# i2c_7_segx4_display.net
KiCad netlist of a schematic drawn in EAGLE
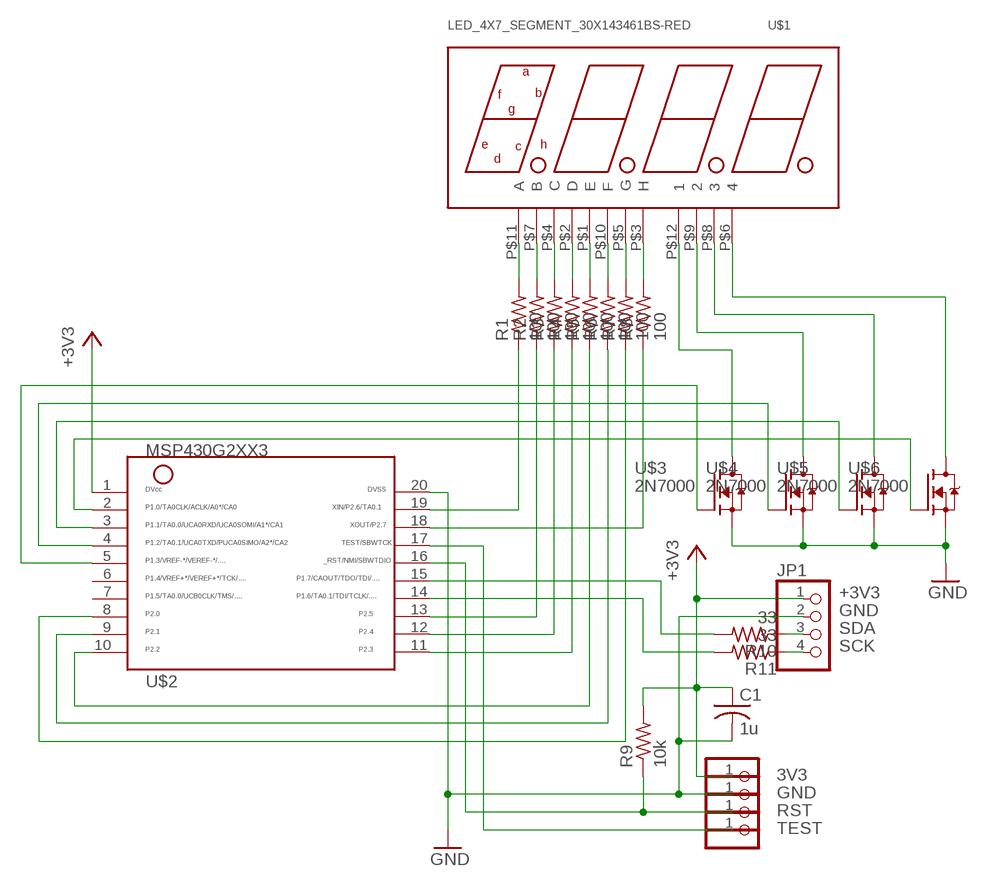
[diagram p0: schematic, sheet 1]

(export (version "E")
  (design (tool "Eeschema 10.0.6"))
  (components
    (comp (ref "3V3")
      (value "PINHD-1X1")
      (footprint "eagle-import:1X01")
      (libsource (lib "eagle-import") (part "PINHD-1X1"))
    )
    (comp (ref "C1")
      (value "1u")
      (footprint "eagle-import:C0805K")
      (libsource (lib "eagle-import") (part "C-USC0805K"))
    )
    (comp (ref "GND")
      (value "PINHD-1X1")
      (footprint "eagle-import:1X01")
      (libsource (lib "eagle-import") (part "PINHD-1X1"))
    )
    (comp (ref "JP1")
      (value "PINHD-1X4")
      (footprint "eagle-import:1X04")
      (libsource (lib "eagle-import") (part "PINHD-1X4"))
    )
    (comp (ref "R1")
      (value "100")
      (footprint "eagle-import:R0603")
      (libsource (lib "eagle-import") (part "R-US_R0603"))
    )
    (comp (ref "R2")
      (value "100")
      (footprint "eagle-import:R0603")
      (libsource (lib "eagle-import") (part "R-US_R0603"))
    )
    (comp (ref "R3")
      (value "100")
      (footprint "eagle-import:R0603")
      (libsource (lib "eagle-import") (part "R-US_R0603"))
    )
    (comp (ref "R4")
      (value "100")
      (footprint "eagle-import:R0603")
      (libsource (lib "eagle-import") (part "R-US_R0603"))
    )
    (comp (ref "R5")
      (value "100")
      (footprint "eagle-import:R0603")
      (libsource (lib "eagle-import") (part "R-US_R0603"))
    )
    (comp (ref "R6")
      (value "100")
      (footprint "eagle-import:R0603")
      (libsource (lib "eagle-import") (part "R-US_R0603"))
    )
    (comp (ref "R7")
      (value "100")
      (footprint "eagle-import:R0603")
      (libsource (lib "eagle-import") (part "R-US_R0603"))
    )
    (comp (ref "R8")
      (value "100")
      (footprint "eagle-import:R0603")
      (libsource (lib "eagle-import") (part "R-US_R0603"))
    )
    (comp (ref "R9")
      (value "10k")
      (footprint "eagle-import:R0603")
      (libsource (lib "eagle-import") (part "R-US_R0603"))
    )
    (comp (ref "R10")
      (value "33")
      (footprint "eagle-import:R0603")
      (libsource (lib "eagle-import") (part "R-US_R0603"))
    )
    (comp (ref "R11")
      (value "33")
      (footprint "eagle-import:R0603")
      (libsource (lib "eagle-import") (part "R-US_R0603"))
    )
    (comp (ref "RST")
      (value "PINHD-1X1")
      (footprint "eagle-import:1X01")
      (libsource (lib "eagle-import") (part "PINHD-1X1"))
    )
    (comp (ref "TEST")
      (value "PINHD-1X1")
      (footprint "eagle-import:1X01")
      (libsource (lib "eagle-import") (part "PINHD-1X1"))
    )
    (comp (ref "U$1")
      (value "LED_4X7_SEGMENT_30X143461BS-RED")
      (footprint "eagle-import:LED_4X7_SEGMENT_30X14")
      (libsource (lib "eagle-import") (part "LED_4X7_SEGMENT_30X143461BS-RED"))
    )
    (comp (ref "U$2")
      (value "G2553")
      (footprint "eagle-import:PW20")
      (libsource (lib "eagle-import") (part "G2XX3---PW20"))
    )
    (comp (ref "U$3")
      (value "2N7000")
      (footprint "eagle-import:SOT23")
      (libsource (lib "eagle-import") (part "2N7000"))
    )
    (comp (ref "U$4")
      (value "2N7000")
      (footprint "eagle-import:SOT23")
      (libsource (lib "eagle-import") (part "2N7000"))
    )
    (comp (ref "U$5")
      (value "2N7000")
      (footprint "eagle-import:SOT23")
      (libsource (lib "eagle-import") (part "2N7000"))
    )
    (comp (ref "U$6")
      (value "2N7000")
      (footprint "eagle-import:SOT23")
      (libsource (lib "eagle-import") (part "2N7000"))
    )
  )
  (nets
    (net (code "1") (name "+3V3") (class "Default")
      (node (ref "3V3") (pin "1") (pinfunction "1_1") (pintype "passive"))
      (node (ref "C1") (pin "1") (pinfunction "1_1") (pintype "passive"))
      (node (ref "JP1") (pin "1") (pinfunction "1_1") (pintype "passive"))
      (node (ref "R9") (pin "2") (pinfunction "2_2") (pintype "passive"))
      (node (ref "U$2") (pin "1") (pinfunction "1_1") (pintype "bidirectional"))
    )
    (net (code "2") (name "/SCK") (class "Default")
      (node (ref "JP1") (pin "4") (pinfunction "4_4") (pintype "passive"))
      (node (ref "R11") (pin "1") (pinfunction "1_1") (pintype "passive"))
    )
    (net (code "3") (name "/SDA") (class "Default")
      (node (ref "JP1") (pin "3") (pinfunction "3_3") (pintype "passive"))
      (node (ref "R10") (pin "1") (pinfunction "1_1") (pintype "passive"))
    )
    (net (code "4") (name "GND") (class "Default")
      (node (ref "C1") (pin "2") (pinfunction "2_2") (pintype "passive"))
      (node (ref "GND") (pin "1") (pinfunction "1_1") (pintype "passive"))
      (node (ref "JP1") (pin "2") (pinfunction "2_2") (pintype "passive"))
      (node (ref "U$2") (pin "20") (pinfunction "20_20") (pintype "bidirectional"))
      (node (ref "U$3") (pin "2") (pinfunction "S_2") (pintype "passive"))
      (node (ref "U$4") (pin "2") (pinfunction "S_2") (pintype "passive"))
      (node (ref "U$5") (pin "2") (pinfunction "S_2") (pintype "passive"))
      (node (ref "U$6") (pin "2") (pinfunction "S_2") (pintype "passive"))
    )
    (net (code "5") (name "Net-(R1-Pad1)") (class "Default")
      (node (ref "R1") (pin "1") (pinfunction "1_1") (pintype "passive"))
      (node (ref "U$2") (pin "19") (pinfunction "19_19") (pintype "bidirectional"))
    )
    (net (code "6") (name "Net-(R2-Pad1)") (class "Default")
      (node (ref "R2") (pin "1") (pinfunction "1_1") (pintype "passive"))
      (node (ref "U$2") (pin "13") (pinfunction "13_13") (pintype "bidirectional"))
    )
    (net (code "7") (name "Net-(R3-Pad1)") (class "Default")
      (node (ref "R3") (pin "1") (pinfunction "1_1") (pintype "passive"))
      (node (ref "U$2") (pin "12") (pinfunction "12_12") (pintype "bidirectional"))
    )
    (net (code "8") (name "Net-(R4-Pad1)") (class "Default")
      (node (ref "R4") (pin "1") (pinfunction "1_1") (pintype "passive"))
      (node (ref "U$2") (pin "11") (pinfunction "11_11") (pintype "bidirectional"))
    )
    (net (code "9") (name "Net-(R5-Pad1)") (class "Default")
      (node (ref "R5") (pin "1") (pinfunction "1_1") (pintype "passive"))
      (node (ref "U$2") (pin "10") (pinfunction "10_10") (pintype "bidirectional"))
    )
    (net (code "10") (name "Net-(R6-Pad1)") (class "Default")
      (node (ref "R6") (pin "1") (pinfunction "1_1") (pintype "passive"))
      (node (ref "U$2") (pin "9") (pinfunction "9_9") (pintype "bidirectional"))
    )
    (net (code "11") (name "Net-(R7-Pad1)") (class "Default")
      (node (ref "R7") (pin "1") (pinfunction "1_1") (pintype "passive"))
      (node (ref "U$2") (pin "8") (pinfunction "8_8") (pintype "bidirectional"))
    )
    (net (code "12") (name "Net-(R8-Pad1)") (class "Default")
      (node (ref "R8") (pin "1") (pinfunction "1_1") (pintype "passive"))
      (node (ref "U$2") (pin "18") (pinfunction "18_18") (pintype "bidirectional"))
    )
    (net (code "13") (name "Net-(R9-Pad1)") (class "Default")
      (node (ref "R9") (pin "1") (pinfunction "1_1") (pintype "passive"))
      (node (ref "RST") (pin "1") (pinfunction "1_1") (pintype "passive"))
      (node (ref "U$2") (pin "16") (pinfunction "16_16") (pintype "bidirectional"))
    )
    (net (code "14") (name "Net-(R10-Pad2)") (class "Default")
      (node (ref "R10") (pin "2") (pinfunction "2_2") (pintype "passive"))
      (node (ref "U$2") (pin "15") (pinfunction "15_15") (pintype "bidirectional"))
    )
    (net (code "15") (name "Net-(R11-Pad2)") (class "Default")
      (node (ref "R11") (pin "2") (pinfunction "2_2") (pintype "passive"))
      (node (ref "U$2") (pin "14") (pinfunction "14_14") (pintype "bidirectional"))
    )
    (net (code "16") (name "Net-(TEST-Pad1)") (class "Default")
      (node (ref "TEST") (pin "1") (pinfunction "1_1") (pintype "passive"))
      (node (ref "U$2") (pin "17") (pinfunction "17_17") (pintype "bidirectional"))
    )
    (net (code "17") (name "Net-(U$1-1)") (class "Default")
      (node (ref "U$1") (pin "P$12") (pinfunction "1_P$12") (pintype "bidirectional"))
      (node (ref "U$3") (pin "3") (pinfunction "D_3") (pintype "passive"))
    )
    (net (code "18") (name "Net-(U$1-2)") (class "Default")
      (node (ref "U$1") (pin "P$9") (pinfunction "2_P$9") (pintype "bidirectional"))
      (node (ref "U$4") (pin "3") (pinfunction "D_3") (pintype "passive"))
    )
    (net (code "19") (name "Net-(U$1-3)") (class "Default")
      (node (ref "U$1") (pin "P$8") (pinfunction "3_P$8") (pintype "bidirectional"))
      (node (ref "U$5") (pin "3") (pinfunction "D_3") (pintype "passive"))
    )
    (net (code "20") (name "Net-(U$1-4)") (class "Default")
      (node (ref "U$1") (pin "P$6") (pinfunction "4_P$6") (pintype "bidirectional"))
      (node (ref "U$6") (pin "3") (pinfunction "D_3") (pintype "passive"))
    )
    (net (code "21") (name "Net-(U$1-A)") (class "Default")
      (node (ref "R1") (pin "2") (pinfunction "2_2") (pintype "passive"))
      (node (ref "U$1") (pin "P$11") (pinfunction "A_P$11") (pintype "bidirectional"))
    )
    (net (code "22") (name "Net-(U$1-B)") (class "Default")
      (node (ref "R2") (pin "2") (pinfunction "2_2") (pintype "passive"))
      (node (ref "U$1") (pin "P$7") (pinfunction "B_P$7") (pintype "bidirectional"))
    )
    (net (code "23") (name "Net-(U$1-C)") (class "Default")
      (node (ref "R3") (pin "2") (pinfunction "2_2") (pintype "passive"))
      (node (ref "U$1") (pin "P$4") (pinfunction "C_P$4") (pintype "bidirectional"))
    )
    (net (code "24") (name "Net-(U$1-D)") (class "Default")
      (node (ref "R4") (pin "2") (pinfunction "2_2") (pintype "passive"))
      (node (ref "U$1") (pin "P$2") (pinfunction "D_P$2") (pintype "bidirectional"))
    )
    (net (code "25") (name "Net-(U$1-E)") (class "Default")
      (node (ref "R5") (pin "2") (pinfunction "2_2") (pintype "passive"))
      (node (ref "U$1") (pin "P$1") (pinfunction "E_P$1") (pintype "bidirectional"))
    )
    (net (code "26") (name "Net-(U$1-F)") (class "Default")
      (node (ref "R6") (pin "2") (pinfunction "2_2") (pintype "passive"))
      (node (ref "U$1") (pin "P$10") (pinfunction "F_P$10") (pintype "bidirectional"))
    )
    (net (code "27") (name "Net-(U$1-G)") (class "Default")
      (node (ref "R7") (pin "2") (pinfunction "2_2") (pintype "passive"))
      (node (ref "U$1") (pin "P$5") (pinfunction "G_P$5") (pintype "bidirectional"))
    )
    (net (code "28") (name "Net-(U$1-H)") (class "Default")
      (node (ref "R8") (pin "2") (pinfunction "2_2") (pintype "passive"))
      (node (ref "U$1") (pin "P$3") (pinfunction "H_P$3") (pintype "bidirectional"))
    )
    (net (code "29") (name "Net-(U$3-G)") (class "Default")
      (node (ref "U$2") (pin "5") (pinfunction "5_5") (pintype "bidirectional"))
      (node (ref "U$3") (pin "1") (pinfunction "G_1") (pintype "passive"))
    )
    (net (code "30") (name "Net-(U$4-G)") (class "Default")
      (node (ref "U$2") (pin "4") (pinfunction "4_4") (pintype "bidirectional"))
      (node (ref "U$4") (pin "1") (pinfunction "G_1") (pintype "passive"))
    )
    (net (code "31") (name "Net-(U$5-G)") (class "Default")
      (node (ref "U$2") (pin "3") (pinfunction "3_3") (pintype "bidirectional"))
      (node (ref "U$5") (pin "1") (pinfunction "G_1") (pintype "passive"))
    )
    (net (code "32") (name "Net-(U$6-G)") (class "Default")
      (node (ref "U$2") (pin "2") (pinfunction "2_2") (pintype "bidirectional"))
      (node (ref "U$6") (pin "1") (pinfunction "G_1") (pintype "passive"))
    )
    (net (code "33") (name "unconnected-(U$2-Pad6)") (class "Default")
      (node (ref "U$2") (pin "6") (pinfunction "6_6") (pintype "bidirectional"))
    )
    (net (code "34") (name "unconnected-(U$2-Pad7)") (class "Default")
      (node (ref "U$2") (pin "7") (pinfunction "7_7") (pintype "bidirectional"))
    )
  )
)
